# ch559.net
KiCad netlist of a schematic drawn in Altium Designer
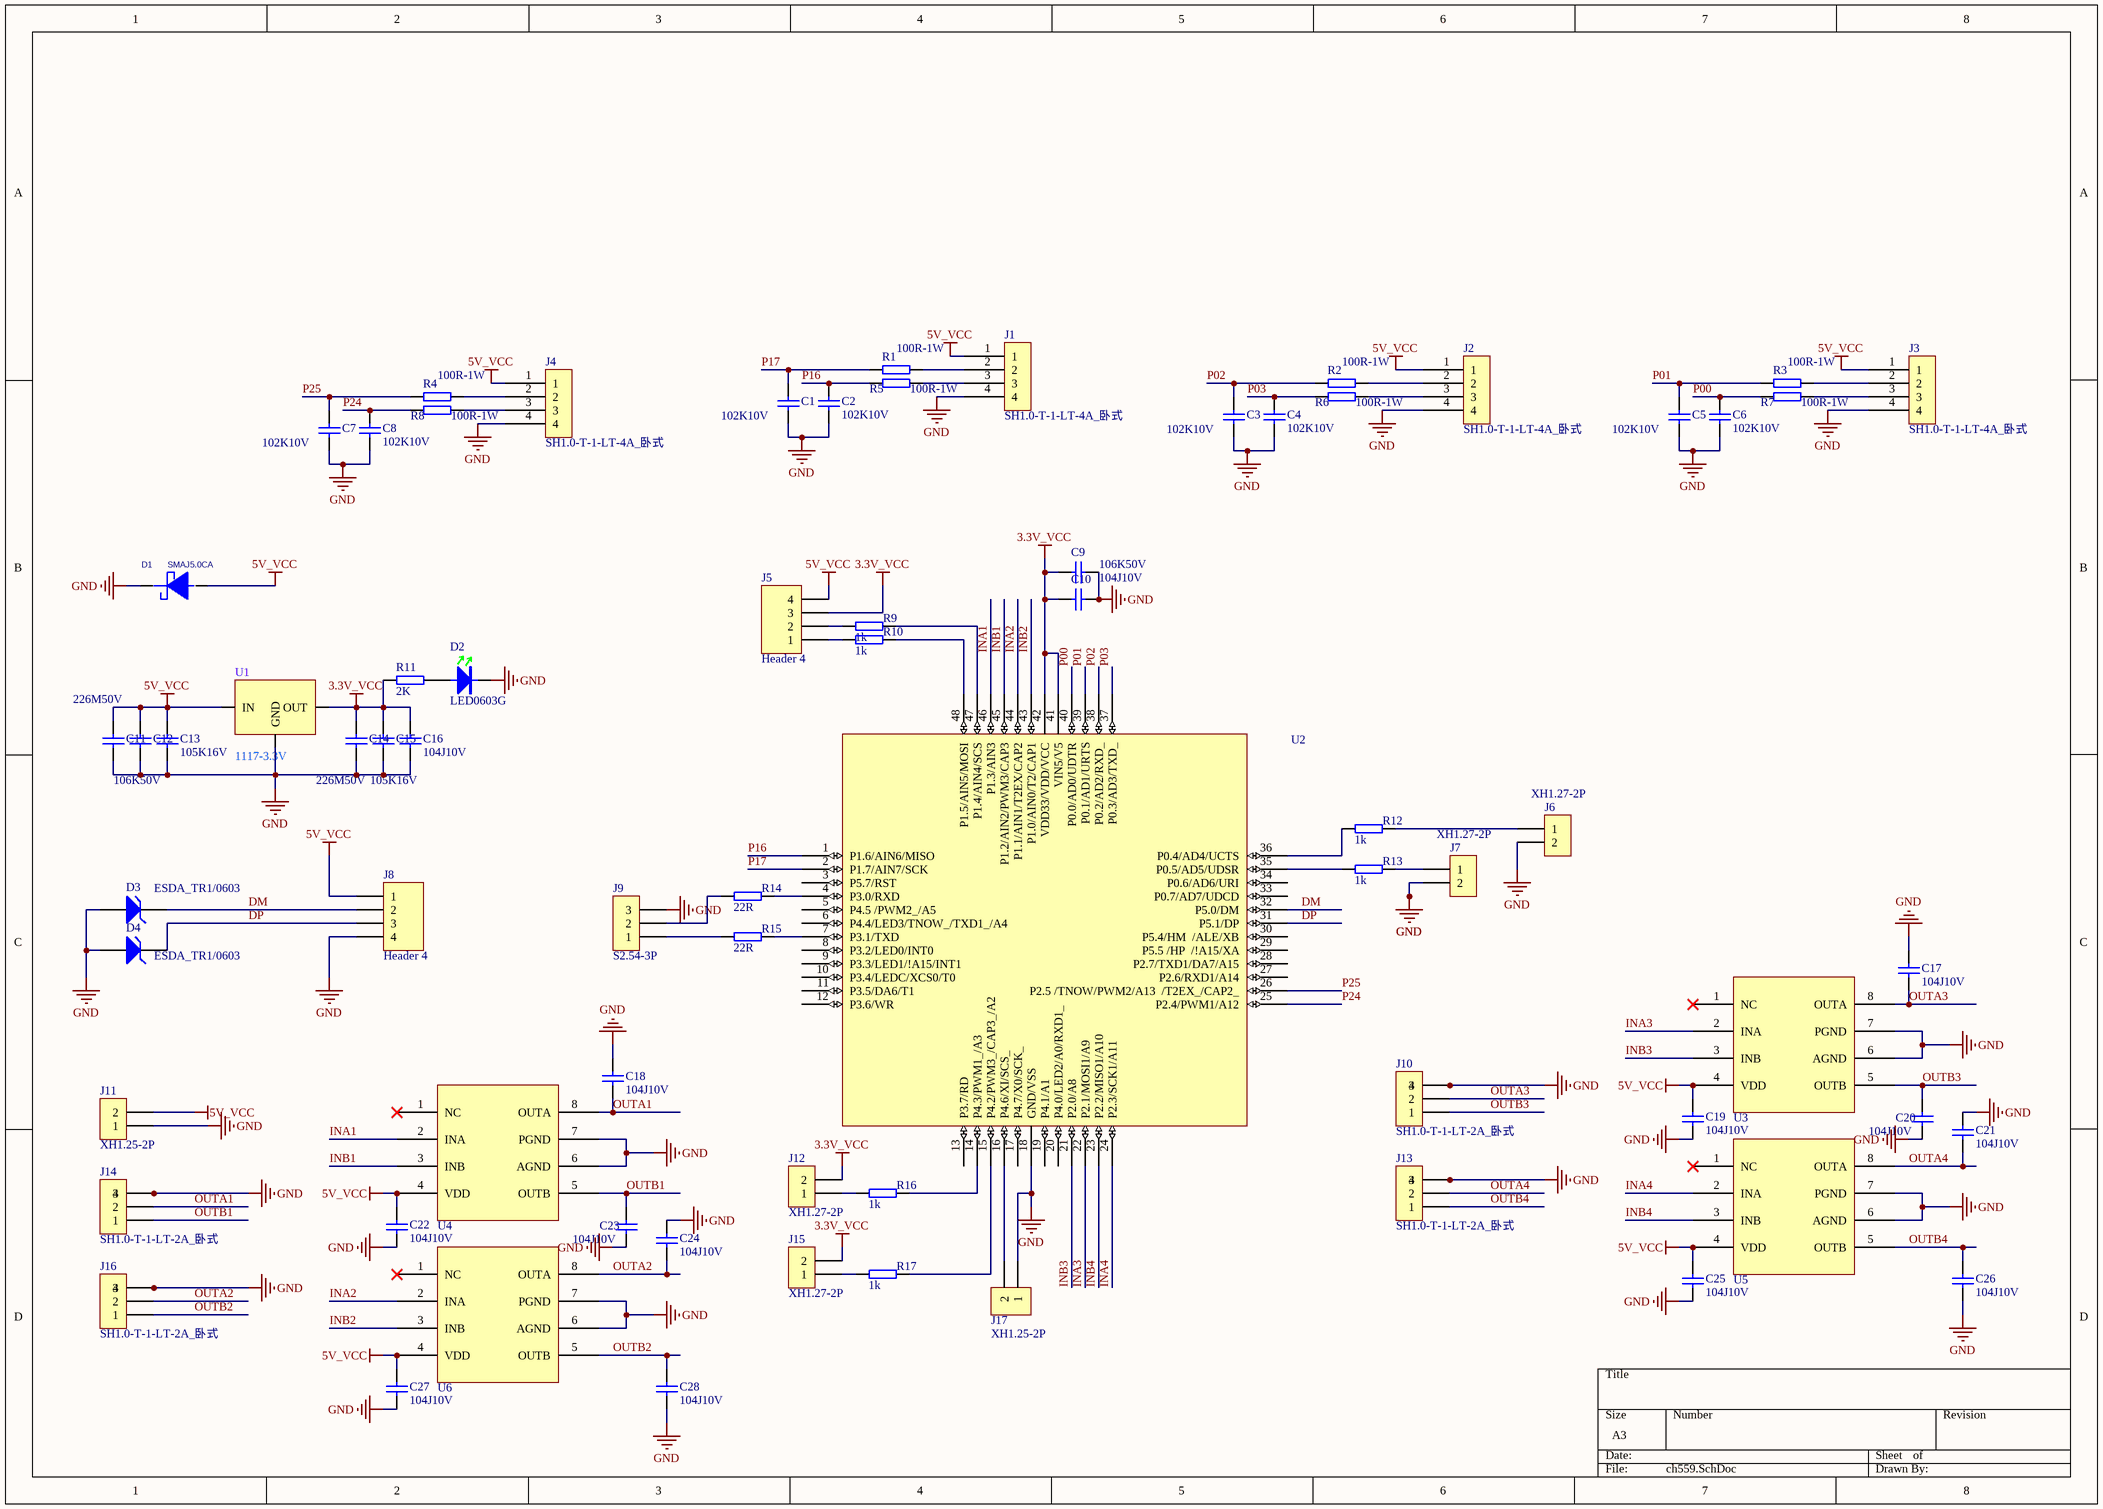
[diagram p0: ch559.SchDoc]

(export (version "E")
  (design (tool "Eeschema 10.0.6"))
  (components
    (comp (ref "C1")
      (value "102K10V")
      (footprint "C0603")
      (description "贴片电容-陶瓷")
      (libsource (lib "Capacitor") (part "C0603X7R-102K10V"))
    )
    (comp (ref "C2")
      (value "102K10V")
      (footprint "C0603")
      (description "贴片电容-陶瓷")
      (libsource (lib "Capacitor") (part "C0603X7R-102K10V"))
    )
    (comp (ref "C3")
      (value "102K10V")
      (footprint "C0603")
      (description "贴片电容-陶瓷")
      (libsource (lib "Capacitor") (part "C0603X7R-102K10V"))
    )
    (comp (ref "C4")
      (value "102K10V")
      (footprint "C0603")
      (description "贴片电容-陶瓷")
      (libsource (lib "Capacitor") (part "C0603X7R-102K10V"))
    )
    (comp (ref "C5")
      (value "102K10V")
      (footprint "C0603")
      (description "贴片电容-陶瓷")
      (libsource (lib "Capacitor") (part "C0603X7R-102K10V"))
    )
    (comp (ref "C6")
      (value "102K10V")
      (footprint "C0603")
      (description "贴片电容-陶瓷")
      (libsource (lib "Capacitor") (part "C0603X7R-102K10V"))
    )
    (comp (ref "C7")
      (value "102K10V")
      (footprint "C0603")
      (description "贴片电容-陶瓷")
      (libsource (lib "Capacitor") (part "C0603X7R-102K10V"))
    )
    (comp (ref "C8")
      (value "102K10V")
      (footprint "C0603")
      (description "贴片电容-陶瓷")
      (libsource (lib "Capacitor") (part "C0603X7R-102K10V"))
    )
    (comp (ref "C9")
      (value "106K50V")
      (footprint "C0603")
      (description "贴片电容-陶瓷")
      (libsource (lib "AIWAC-bolsterV01") (part "C0603X7R-106K50V"))
    )
    (comp (ref "C10")
      (value "104J10V")
      (footprint "C0402")
      (description "贴片电容-陶瓷")
      (libsource (lib "AIWAC-bolsterV01") (part "C0402X7R-104J10V"))
    )
    (comp (ref "C11")
      (value "226M50V")
      (footprint "C0805")
      (description "贴片电容-陶瓷")
      (libsource (lib "AIWAC-bolsterV01") (part "C0805Y5V-226M50V"))
    )
    (comp (ref "C12")
      (value "106K50V")
      (footprint "C0603")
      (description "贴片电容-陶瓷")
      (libsource (lib "AIWAC-bolsterV01") (part "C0603X7R-106K50V"))
    )
    (comp (ref "C13")
      (value "105K16V")
      (footprint "C0603")
      (description "贴片电容-陶瓷")
      (libsource (lib "AIWAC-bolsterV01") (part "C0603X7R-105K16V"))
    )
    (comp (ref "C14")
      (value "226M50V")
      (footprint "C0805")
      (description "贴片电容-陶瓷")
      (libsource (lib "AIWAC-bolsterV01") (part "C0805Y5V-226M50V"))
    )
    (comp (ref "C15")
      (value "105K16V")
      (footprint "C0603")
      (description "贴片电容-陶瓷")
      (libsource (lib "AIWAC-bolsterV01") (part "C0603X7R-105K16V"))
    )
    (comp (ref "C16")
      (value "104J10V")
      (footprint "C0402")
      (description "贴片电容-陶瓷")
      (libsource (lib "AIWAC-bolsterV01") (part "C0402X7R-104J10V"))
    )
    (comp (ref "C17")
      (value "104J10V")
      (footprint "C0402")
      (description "贴片电容-陶瓷")
      (libsource (lib "AIWAC-bolsterV01") (part "C0402X7R-104J10V"))
    )
    (comp (ref "C18")
      (value "104J10V")
      (footprint "C0402")
      (description "贴片电容-陶瓷")
      (libsource (lib "AIWAC-bolsterV01") (part "C0402X7R-104J10V"))
    )
    (comp (ref "C19")
      (value "104J10V")
      (footprint "C0402")
      (description "贴片电容-陶瓷")
      (libsource (lib "AIWAC-bolsterV01") (part "C0402X7R-104J10V"))
    )
    (comp (ref "C20")
      (value "104J10V")
      (footprint "C0402")
      (description "贴片电容-陶瓷")
      (libsource (lib "AIWAC-bolsterV01") (part "C0402X7R-104J10V"))
    )
    (comp (ref "C21")
      (value "104J10V")
      (footprint "C0402")
      (description "贴片电容-陶瓷")
      (libsource (lib "AIWAC-bolsterV01") (part "C0402X7R-104J10V"))
    )
    (comp (ref "C22")
      (value "104J10V")
      (footprint "C0402")
      (description "贴片电容-陶瓷")
      (libsource (lib "AIWAC-bolsterV01") (part "C0402X7R-104J10V"))
    )
    (comp (ref "C23")
      (value "104J10V")
      (footprint "C0402")
      (description "贴片电容-陶瓷")
      (libsource (lib "AIWAC-bolsterV01") (part "C0402X7R-104J10V"))
    )
    (comp (ref "C24")
      (value "104J10V")
      (footprint "C0402")
      (description "贴片电容-陶瓷")
      (libsource (lib "AIWAC-bolsterV01") (part "C0402X7R-104J10V"))
    )
    (comp (ref "C25")
      (value "104J10V")
      (footprint "C0402")
      (description "贴片电容-陶瓷")
      (libsource (lib "AIWAC-bolsterV01") (part "C0402X7R-104J10V"))
    )
    (comp (ref "C26")
      (value "104J10V")
      (footprint "C0402")
      (description "贴片电容-陶瓷")
      (libsource (lib "AIWAC-bolsterV01") (part "C0402X7R-104J10V"))
    )
    (comp (ref "C27")
      (value "104J10V")
      (footprint "C0402")
      (description "贴片电容-陶瓷")
      (libsource (lib "AIWAC-bolsterV01") (part "C0402X7R-104J10V"))
    )
    (comp (ref "C28")
      (value "104J10V")
      (footprint "C0402")
      (description "贴片电容-陶瓷")
      (libsource (lib "AIWAC-bolsterV01") (part "C0402X7R-104J10V"))
    )
    (comp (ref "D1") (value "SMAJ5.0CA") (footprint "DO-214") (libsource (lib "ISO-V3") (part "SMAJ5.0CA")))
    (comp (ref "D2")
      (value "LED0603G")
      (footprint "D-LED0603G")
      (description "贴片二极管-LED")
      (libsource (lib "AIWAC-bolsterV01") (part "DLED-0603-G"))
    )
    (comp (ref "D3")
      (value "ESDA_TR1/0603")
      (footprint "HS_0603D")
      (description "Zener Diode")
      (fields (field (name "PUBLISHER") "*"))
      (libsource (lib "HSC32K1(QFN56)_BlueTooth_V2.0_20171108 - 副本") (part "D Zener"))
    )
    (comp (ref "D4")
      (value "ESDA_TR1/0603")
      (footprint "HS_0603D")
      (description "Zener Diode")
      (fields (field (name "PUBLISHER") "*"))
      (libsource (lib "HSC32K1(QFN56)_BlueTooth_V2.0_20171108 - 副本") (part "D Zener"))
    )
    (comp (ref "J1")
      (value "SH1.0-T-1-LT-4A_卧式")
      (footprint "XH2.54-4P")
      (libsource (lib "Schlib1") (part "SH1.0-T-1-LT-4A_卧式"))
    )
    (comp (ref "J2")
      (value "SH1.0-T-1-LT-4A_卧式")
      (footprint "XH2.54-4P")
      (libsource (lib "Schlib1") (part "SH1.0-T-1-LT-4A_卧式"))
    )
    (comp (ref "J3")
      (value "SH1.0-T-1-LT-4A_卧式")
      (footprint "XH2.54-4P")
      (libsource (lib "Schlib1") (part "SH1.0-T-1-LT-4A_卧式"))
    )
    (comp (ref "J4")
      (value "SH1.0-T-1-LT-4A_卧式")
      (footprint "XH2.54-4P")
      (libsource (lib "Schlib1") (part "SH1.0-T-1-LT-4A_卧式"))
    )
    (comp (ref "J5")
      (value "Header 4")
      (footprint "J-SH1.27 -4")
      (description "Header, 4-Pin")
      (fields (field (name "PUBLISHER") "Altium Limited"))
      (libsource (lib "USB_COM_V1.0") (part "Header 4"))
    )
    (comp (ref "J6")
      (value "XH1.27-2P")
      (footprint "J-SH1.27-2")
      (description "接插件-1.27")
      (libsource (lib "") (part "J-XH1.27-2P_1"))
    )
    (comp (ref "J7")
      (value "XH1.27-2P")
      (footprint "J-SH1.27-2")
      (description "接插件-1.27")
      (libsource (lib "") (part "J-XH1.27-2P_1"))
    )
    (comp (ref "J8")
      (value "Header 4")
      (footprint "XH2.54-4P")
      (description "Header, 4-Pin")
      (fields (field (name "PUBLISHER") "Altium Limited"))
      (libsource (lib "Miscellaneous Connectors") (part "Header 4"))
    )
    (comp (ref "J9")
      (value "S2.54-3P")
      (footprint "S2.54-3P")
      (description "单排排针-直针")
      (libsource (lib "PCB_Project") (part "J-S2.54-3P"))
    )
    (comp (ref "J10")
      (value "SH1.0-T-1-LT-2A_卧式")
      (footprint "J-SH2.0-T-1-LT-2A_立式")
      (libsource (lib "Connector") (part "SH1.0-T-1-LT-2A_卧式"))
    )
    (comp (ref "J11")
      (value "XH1.25-2P")
      (footprint "XH2.54-2p")
      (description "接插件-2.54")
      (libsource (lib "USB_COM_V1.0") (part "J-XH2.54-2P_1"))
    )
    (comp (ref "J12")
      (value "XH1.27-2P")
      (footprint "J-SH1.27-2")
      (description "接插件-1.27")
      (libsource (lib "USB_COM_V1.0") (part "J-XH1.27-2P"))
    )
    (comp (ref "J13")
      (value "SH1.0-T-1-LT-2A_卧式")
      (footprint "J-SH2.0-T-1-LT-2A_立式")
      (libsource (lib "Connector") (part "SH1.0-T-1-LT-2A_卧式"))
    )
    (comp (ref "J14")
      (value "SH1.0-T-1-LT-2A_卧式")
      (footprint "J-SH2.0-T-1-LT-2A_立式")
      (libsource (lib "Connector") (part "SH1.0-T-1-LT-2A_卧式"))
    )
    (comp (ref "J15")
      (value "XH1.27-2P")
      (footprint "J-SH1.27-2")
      (description "接插件-1.27")
      (libsource (lib "USB_COM_V1.0") (part "J-XH1.27-2P"))
    )
    (comp (ref "J16")
      (value "SH1.0-T-1-LT-2A_卧式")
      (footprint "J-SH2.0-T-1-LT-2A_立式")
      (libsource (lib "Connector") (part "SH1.0-T-1-LT-2A_卧式"))
    )
    (comp (ref "J17")
      (value "XH1.25-2P")
      (footprint "S1.25-2P")
      (description "接插件-2.54")
      (libsource (lib "AIWAC-bolsterV01") (part "J-XH2.54-2P"))
    )
    (comp (ref "R1")
      (value "100R-1W")
      (footprint "R0603")
      (description "插件电阻-碳膜")
      (libsource (lib "Resistor") (part "R1-100R"))
    )
    (comp (ref "R2")
      (value "100R-1W")
      (footprint "R0603")
      (description "插件电阻-碳膜")
      (libsource (lib "Resistor") (part "R1-100R"))
    )
    (comp (ref "R3")
      (value "100R-1W")
      (footprint "R0603")
      (description "插件电阻-碳膜")
      (libsource (lib "Resistor") (part "R1-100R"))
    )
    (comp (ref "R4")
      (value "100R-1W")
      (footprint "R0603")
      (description "插件电阻-碳膜")
      (libsource (lib "Resistor") (part "R1-100R"))
    )
    (comp (ref "R5")
      (value "100R-1W")
      (footprint "R0603")
      (description "插件电阻-碳膜")
      (libsource (lib "Resistor") (part "R1-100R"))
    )
    (comp (ref "R6")
      (value "100R-1W")
      (footprint "R0603")
      (description "插件电阻-碳膜")
      (libsource (lib "Resistor") (part "R1-100R"))
    )
    (comp (ref "R7")
      (value "100R-1W")
      (footprint "R0603")
      (description "插件电阻-碳膜")
      (libsource (lib "Resistor") (part "R1-100R"))
    )
    (comp (ref "R8")
      (value "100R-1W")
      (footprint "R0603")
      (description "插件电阻-碳膜")
      (libsource (lib "Resistor") (part "R1-100R"))
    )
    (comp (ref "R9")
      (value "1k")
      (footprint "R0603")
      (description "贴片电阻-通用")
      (libsource (lib "Resistor") (part "R0603-100RF"))
    )
    (comp (ref "R10")
      (value "1k")
      (footprint "R0603")
      (description "贴片电阻-通用")
      (libsource (lib "Resistor") (part "R0603-100RF"))
    )
    (comp (ref "R11")
      (value "2K")
      (footprint "R0603")
      (description "贴片电阻-通用")
      (libsource (lib "Resistor") (part "R0603-100RF"))
    )
    (comp (ref "R12")
      (value "1k")
      (footprint "R0603")
      (description "贴片电阻-通用")
      (libsource (lib "Resistor") (part "R0603-100RF"))
    )
    (comp (ref "R13")
      (value "1k")
      (footprint "R0603")
      (description "贴片电阻-通用")
      (libsource (lib "Resistor") (part "R0603-100RF"))
    )
    (comp (ref "R14")
      (value "22R")
      (footprint "R0603")
      (description "贴片电阻-通用")
      (libsource (lib "Resistor") (part "R0603-100RF"))
    )
    (comp (ref "R15")
      (value "22R")
      (footprint "R0603")
      (description "贴片电阻-通用")
      (libsource (lib "Resistor") (part "R0603-100RF"))
    )
    (comp (ref "R16")
      (value "1k")
      (footprint "R0603")
      (description "贴片电阻-通用")
      (libsource (lib "Resistor") (part "R0603-100RF"))
    )
    (comp (ref "R17")
      (value "1k")
      (footprint "R0603")
      (description "贴片电阻-通用")
      (libsource (lib "Resistor") (part "R0603-100RF"))
    )
    (comp (ref "U1")
      (value "1117-3.3V")
      (footprint "SOT-223")
      (description "芯片 电源类")
      (libsource (lib "标准通用原理图库") (part "AP1117-33 SOT-223"))
    )
    (comp (ref "U2")
      (value "CH559L")
      (footprint "LQFP48")
      (description "单片机")
      (libsource (lib "PCB_Project") (part "CH559L"))
    )
    (comp (ref "U3")
      (value "PTC918")
      (footprint "SO-8")
      (description "马达驱动芯片")
      (libsource (lib "USB_COM_V1.0") (part "PTC918"))
    )
    (comp (ref "U4")
      (value "PTC918")
      (footprint "SO-8")
      (description "马达驱动芯片")
      (libsource (lib "USB_COM_V1.0") (part "PTC918"))
    )
    (comp (ref "U5")
      (value "PTC918")
      (footprint "SO-8")
      (description "马达驱动芯片")
      (libsource (lib "USB_COM_V1.0") (part "PTC918"))
    )
    (comp (ref "U6")
      (value "PTC918")
      (footprint "SO-8")
      (description "马达驱动芯片")
      (libsource (lib "USB_COM_V1.0") (part "PTC918"))
    )
  )
  (nets
    (net (code "1") (name "/DM") (class "Default")
      (node (ref "D3") (pin "2") (pinfunction "K_2") (pintype "passive"))
      (node (ref "J8") (pin "2") (pinfunction "2_2") (pintype "passive"))
      (node (ref "U2") (pin "32") (pinfunction "P5.0/DM_32") (pintype "bidirectional"))
    )
    (net (code "2") (name "/DP") (class "Default")
      (node (ref "D4") (pin "2") (pinfunction "K_2") (pintype "passive"))
      (node (ref "J8") (pin "3") (pinfunction "3_3") (pintype "passive"))
      (node (ref "U2") (pin "31") (pinfunction "P5.1/DP_31") (pintype "bidirectional"))
    )
    (net (code "3") (name "/INA1") (class "Default")
      (node (ref "U2") (pin "46") (pinfunction "P1.3/AIN3_46") (pintype "bidirectional"))
      (node (ref "U4") (pin "2") (pinfunction "INA_2") (pintype "passive"))
    )
    (net (code "4") (name "/INA2") (class "Default")
      (node (ref "U2") (pin "44") (pinfunction "P1.1/AIN1/T2EX/CAP2_44") (pintype "bidirectional"))
      (node (ref "U6") (pin "2") (pinfunction "INA_2") (pintype "passive"))
    )
    (net (code "5") (name "/INA3") (class "Default")
      (node (ref "U2") (pin "22") (pinfunction "P2.1/MOSI1/A9_22") (pintype "bidirectional"))
      (node (ref "U3") (pin "2") (pinfunction "INA_2") (pintype "passive"))
    )
    (net (code "6") (name "/INA4") (class "Default")
      (node (ref "U2") (pin "24") (pinfunction "P2.3/SCK1/A11_24") (pintype "bidirectional"))
      (node (ref "U5") (pin "2") (pinfunction "INA_2") (pintype "passive"))
    )
    (net (code "7") (name "/INB1") (class "Default")
      (node (ref "U2") (pin "45") (pinfunction "P1.2/AIN2/PWM3/CAP3_45") (pintype "bidirectional"))
      (node (ref "U4") (pin "3") (pinfunction "INB_3") (pintype "passive"))
    )
    (net (code "8") (name "/INB2") (class "Default")
      (node (ref "U2") (pin "43") (pinfunction "P1.0/AIN0/T2/CAP1_43") (pintype "bidirectional"))
      (node (ref "U6") (pin "3") (pinfunction "INB_3") (pintype "passive"))
    )
    (net (code "9") (name "/INB3") (class "Default")
      (node (ref "U2") (pin "21") (pinfunction "P2.0/A8_21") (pintype "bidirectional"))
      (node (ref "U3") (pin "3") (pinfunction "INB_3") (pintype "passive"))
    )
    (net (code "10") (name "/INB4") (class "Default")
      (node (ref "U2") (pin "23") (pinfunction "P2.2/MISO1/A10_23") (pintype "bidirectional"))
      (node (ref "U5") (pin "3") (pinfunction "INB_3") (pintype "passive"))
    )
    (net (code "11") (name "/OUTA1") (class "Default")
      (node (ref "C18") (pin "2") (pinfunction "2_2") (pintype "passive"))
      (node (ref "J14") (pin "2") (pinfunction "2_2") (pintype "passive"))
      (node (ref "U4") (pin "8") (pinfunction "OUTA_8") (pintype "passive"))
    )
    (net (code "12") (name "/OUTA2") (class "Default")
      (node (ref "C24") (pin "2") (pinfunction "2_2") (pintype "passive"))
      (node (ref "J16") (pin "2") (pinfunction "2_2") (pintype "passive"))
      (node (ref "U6") (pin "8") (pinfunction "OUTA_8") (pintype "passive"))
    )
    (net (code "13") (name "/OUTA3") (class "Default")
      (node (ref "C17") (pin "2") (pinfunction "2_2") (pintype "passive"))
      (node (ref "J10") (pin "2") (pinfunction "2_2") (pintype "passive"))
      (node (ref "U3") (pin "8") (pinfunction "OUTA_8") (pintype "passive"))
    )
    (net (code "14") (name "/OUTA4") (class "Default")
      (node (ref "C21") (pin "2") (pinfunction "2_2") (pintype "passive"))
      (node (ref "J13") (pin "2") (pinfunction "2_2") (pintype "passive"))
      (node (ref "U5") (pin "8") (pinfunction "OUTA_8") (pintype "passive"))
    )
    (net (code "15") (name "/OUTB1") (class "Default")
      (node (ref "C23") (pin "1") (pinfunction "1_1") (pintype "passive"))
      (node (ref "J14") (pin "1") (pinfunction "1_1") (pintype "passive"))
      (node (ref "U4") (pin "5") (pinfunction "OUTB_5") (pintype "passive"))
    )
    (net (code "16") (name "/OUTB2") (class "Default")
      (node (ref "C28") (pin "1") (pinfunction "1_1") (pintype "passive"))
      (node (ref "J16") (pin "1") (pinfunction "1_1") (pintype "passive"))
      (node (ref "U6") (pin "5") (pinfunction "OUTB_5") (pintype "passive"))
    )
    (net (code "17") (name "/OUTB3") (class "Default")
      (node (ref "C20") (pin "1") (pinfunction "1_1") (pintype "passive"))
      (node (ref "J10") (pin "1") (pinfunction "1_1") (pintype "passive"))
      (node (ref "U3") (pin "5") (pinfunction "OUTB_5") (pintype "passive"))
    )
    (net (code "18") (name "/OUTB4") (class "Default")
      (node (ref "C26") (pin "1") (pinfunction "1_1") (pintype "passive"))
      (node (ref "J13") (pin "1") (pinfunction "1_1") (pintype "passive"))
      (node (ref "U5") (pin "5") (pinfunction "OUTB_5") (pintype "passive"))
    )
    (net (code "19") (name "/P00") (class "Default")
      (node (ref "C6") (pin "1") (pinfunction "1_1") (pintype "passive"))
      (node (ref "R7") (pin "1") (pinfunction "1_1") (pintype "passive"))
      (node (ref "U2") (pin "40") (pinfunction "P0.0/AD0/UDTR_40") (pintype "bidirectional"))
    )
    (net (code "20") (name "/P01") (class "Default")
      (node (ref "C5") (pin "1") (pinfunction "1_1") (pintype "passive"))
      (node (ref "R3") (pin "1") (pinfunction "1_1") (pintype "passive"))
      (node (ref "U2") (pin "39") (pinfunction "P0.1/AD1/URTS_39") (pintype "bidirectional"))
    )
    (net (code "21") (name "/P02") (class "Default")
      (node (ref "C3") (pin "1") (pinfunction "1_1") (pintype "passive"))
      (node (ref "R2") (pin "1") (pinfunction "1_1") (pintype "passive"))
      (node (ref "U2") (pin "38") (pinfunction "P0.2/AD2/RXD__38") (pintype "bidirectional"))
    )
    (net (code "22") (name "/P03") (class "Default")
      (node (ref "C4") (pin "1") (pinfunction "1_1") (pintype "passive"))
      (node (ref "R6") (pin "1") (pinfunction "1_1") (pintype "passive"))
      (node (ref "U2") (pin "37") (pinfunction "P0.3/AD3/TXD__37") (pintype "bidirectional"))
    )
    (net (code "23") (name "/P16") (class "Default")
      (node (ref "C2") (pin "1") (pinfunction "1_1") (pintype "passive"))
      (node (ref "R5") (pin "1") (pinfunction "1_1") (pintype "passive"))
      (node (ref "U2") (pin "1") (pinfunction "P1.6/AIN6/MISO_1") (pintype "bidirectional"))
    )
    (net (code "24") (name "/P17") (class "Default")
      (node (ref "C1") (pin "1") (pinfunction "1_1") (pintype "passive"))
      (node (ref "R1") (pin "1") (pinfunction "1_1") (pintype "passive"))
      (node (ref "U2") (pin "2") (pinfunction "P1.7/AIN7/SCK_2") (pintype "bidirectional"))
    )
    (net (code "25") (name "/P24") (class "Default")
      (node (ref "C8") (pin "1") (pinfunction "1_1") (pintype "passive"))
      (node (ref "R8") (pin "1") (pinfunction "1_1") (pintype "passive"))
      (node (ref "U2") (pin "25") (pinfunction "P2.4/PWM1/A12_25") (pintype "bidirectional"))
    )
    (net (code "26") (name "/P25") (class "Default")
      (node (ref "C7") (pin "1") (pinfunction "1_1") (pintype "passive"))
      (node (ref "R4") (pin "1") (pinfunction "1_1") (pintype "passive"))
      (node (ref "U2") (pin "26") (pinfunction "P2.5_/TNOW/PWM2/A13__/T2EX_/CAP2__26") (pintype "bidirectional"))
    )
    (net (code "27") (name "3.3V_VCC") (class "Default")
      (node (ref "C10") (pin "2") (pinfunction "2_2") (pintype "passive"))
      (node (ref "C14") (pin "1") (pinfunction "1_1") (pintype "passive"))
      (node (ref "C15") (pin "2") (pinfunction "2_2") (pintype "passive"))
      (node (ref "C16") (pin "1") (pinfunction "1_1") (pintype "passive"))
      (node (ref "C9") (pin "2") (pinfunction "2_2") (pintype "passive"))
      (node (ref "J12") (pin "2") (pinfunction "2_2") (pintype "passive"))
      (node (ref "J15") (pin "2") (pinfunction "2_2") (pintype "passive"))
      (node (ref "J5") (pin "3") (pinfunction "3_3") (pintype "passive"))
      (node (ref "R11") (pin "2") (pinfunction "2_2") (pintype "passive"))
      (node (ref "U1") (pin "2") (pinfunction "OUT_2") (pintype "passive"))
      (node (ref "U2") (pin "41") (pinfunction "VIN5/V5_41") (pintype "passive"))
      (node (ref "U2") (pin "42") (pinfunction "VDD33/VDD/VCC_42") (pintype "passive"))
    )
    (net (code "28") (name "5V_VCC") (class "Default")
      (node (ref "C11") (pin "1") (pinfunction "1_1") (pintype "passive"))
      (node (ref "C12") (pin "1") (pinfunction "1_1") (pintype "passive"))
      (node (ref "C13") (pin "1") (pinfunction "1_1") (pintype "passive"))
      (node (ref "C19") (pin "1") (pinfunction "1_1") (pintype "passive"))
      (node (ref "C22") (pin "1") (pinfunction "1_1") (pintype "passive"))
      (node (ref "C25") (pin "1") (pinfunction "1_1") (pintype "passive"))
      (node (ref "C27") (pin "1") (pinfunction "1_1") (pintype "passive"))
      (node (ref "D1") (pin "1") (pinfunction "+_1") (pintype "passive"))
      (node (ref "J1") (pin "1") (pinfunction "1_1") (pintype "passive"))
      (node (ref "J11") (pin "2") (pinfunction "2_2") (pintype "passive"))
      (node (ref "J2") (pin "1") (pinfunction "1_1") (pintype "passive"))
      (node (ref "J3") (pin "1") (pinfunction "1_1") (pintype "passive"))
      (node (ref "J4") (pin "1") (pinfunction "1_1") (pintype "passive"))
      (node (ref "J5") (pin "4") (pinfunction "4_4") (pintype "passive"))
      (node (ref "J8") (pin "1") (pinfunction "1_1") (pintype "passive"))
      (node (ref "U1") (pin "3") (pinfunction "IN_3") (pintype "passive"))
      (node (ref "U3") (pin "4") (pinfunction "VDD_4") (pintype "passive"))
      (node (ref "U4") (pin "4") (pinfunction "VDD_4") (pintype "passive"))
      (node (ref "U5") (pin "4") (pinfunction "VDD_4") (pintype "passive"))
      (node (ref "U6") (pin "4") (pinfunction "VDD_4") (pintype "passive"))
    )
    (net (code "29") (name "GND") (class "Default")
      (node (ref "C1") (pin "2") (pinfunction "2_2") (pintype "passive"))
      (node (ref "C10") (pin "1") (pinfunction "1_1") (pintype "passive"))
      (node (ref "C11") (pin "2") (pinfunction "2_2") (pintype "passive"))
      (node (ref "C12") (pin "2") (pinfunction "2_2") (pintype "passive"))
      (node (ref "C13") (pin "2") (pinfunction "2_2") (pintype "passive"))
      (node (ref "C14") (pin "2") (pinfunction "2_2") (pintype "passive"))
      (node (ref "C15") (pin "1") (pinfunction "1_1") (pintype "passive"))
      (node (ref "C16") (pin "2") (pinfunction "2_2") (pintype "passive"))
      (node (ref "C17") (pin "1") (pinfunction "1_1") (pintype "passive"))
      (node (ref "C18") (pin "1") (pinfunction "1_1") (pintype "passive"))
      (node (ref "C19") (pin "2") (pinfunction "2_2") (pintype "passive"))
      (node (ref "C2") (pin "2") (pinfunction "2_2") (pintype "passive"))
      (node (ref "C20") (pin "2") (pinfunction "2_2") (pintype "passive"))
      (node (ref "C21") (pin "1") (pinfunction "1_1") (pintype "passive"))
      (node (ref "C22") (pin "2") (pinfunction "2_2") (pintype "passive"))
      (node (ref "C23") (pin "2") (pinfunction "2_2") (pintype "passive"))
      (node (ref "C24") (pin "1") (pinfunction "1_1") (pintype "passive"))
      (node (ref "C25") (pin "2") (pinfunction "2_2") (pintype "passive"))
      (node (ref "C26") (pin "2") (pinfunction "2_2") (pintype "passive"))
      (node (ref "C27") (pin "2") (pinfunction "2_2") (pintype "passive"))
      (node (ref "C28") (pin "2") (pinfunction "2_2") (pintype "passive"))
      (node (ref "C3") (pin "2") (pinfunction "2_2") (pintype "passive"))
      (node (ref "C4") (pin "2") (pinfunction "2_2") (pintype "passive"))
      (node (ref "C5") (pin "2") (pinfunction "2_2") (pintype "passive"))
      (node (ref "C6") (pin "2") (pinfunction "2_2") (pintype "passive"))
      (node (ref "C7") (pin "2") (pinfunction "2_2") (pintype "passive"))
      (node (ref "C8") (pin "2") (pinfunction "2_2") (pintype "passive"))
      (node (ref "C9") (pin "1") (pinfunction "1_1") (pintype "passive"))
      (node (ref "D1") (pin "2") (pinfunction "-_2") (pintype "passive"))
      (node (ref "D2") (pin "2") (pinfunction "2_2") (pintype "passive"))
      (node (ref "D3") (pin "1") (pinfunction "A_1") (pintype "passive"))
      (node (ref "D4") (pin "1") (pinfunction "A_1") (pintype "passive"))
      (node (ref "J1") (pin "4") (pinfunction "4_4") (pintype "passive"))
      (node (ref "J10") (pin "3") (pinfunction "3_3") (pintype "passive"))
      (node (ref "J10") (pin "4") (pinfunction "4_4") (pintype "passive"))
      (node (ref "J11") (pin "1") (pinfunction "1_1") (pintype "passive"))
      (node (ref "J13") (pin "3") (pinfunction "3_3") (pintype "passive"))
      (node (ref "J13") (pin "4") (pinfunction "4_4") (pintype "passive"))
      (node (ref "J14") (pin "3") (pinfunction "3_3") (pintype "passive"))
      (node (ref "J14") (pin "4") (pinfunction "4_4") (pintype "passive"))
      (node (ref "J16") (pin "3") (pinfunction "3_3") (pintype "passive"))
      (node (ref "J16") (pin "4") (pinfunction "4_4") (pintype "passive"))
      (node (ref "J17") (pin "1") (pinfunction "1_1") (pintype "passive"))
      (node (ref "J2") (pin "4") (pinfunction "4_4") (pintype "passive"))
      (node (ref "J3") (pin "4") (pinfunction "4_4") (pintype "passive"))
      (node (ref "J4") (pin "4") (pinfunction "4_4") (pintype "passive"))
      (node (ref "J6") (pin "2") (pinfunction "2_2") (pintype "passive"))
      (node (ref "J7") (pin "2") (pinfunction "2_2") (pintype "passive"))
      (node (ref "J8") (pin "4") (pinfunction "4_4") (pintype "passive"))
      (node (ref "J9") (pin "3") (pinfunction "3_3") (pintype "passive"))
      (node (ref "U1") (pin "1") (pinfunction "GND_1") (pintype "passive"))
      (node (ref "U2") (pin "18") (pinfunction "GND/VSS_18") (pintype "passive"))
      (node (ref "U3") (pin "6") (pinfunction "AGND_6") (pintype "passive"))
      (node (ref "U3") (pin "7") (pinfunction "PGND_7") (pintype "passive"))
      (node (ref "U4") (pin "6") (pinfunction "AGND_6") (pintype "passive"))
      (node (ref "U4") (pin "7") (pinfunction "PGND_7") (pintype "passive"))
      (node (ref "U5") (pin "6") (pinfunction "AGND_6") (pintype "passive"))
      (node (ref "U5") (pin "7") (pinfunction "PGND_7") (pintype "passive"))
      (node (ref "U6") (pin "6") (pinfunction "AGND_6") (pintype "passive"))
      (node (ref "U6") (pin "7") (pinfunction "PGND_7") (pintype "passive"))
    )
    (net (code "30") (name "Net-(D2-Pad1)") (class "Default")
      (node (ref "D2") (pin "1") (pinfunction "1_1") (pintype "passive"))
      (node (ref "R11") (pin "1") (pinfunction "1_1") (pintype "passive"))
    )
    (net (code "31") (name "Net-(J1-Pad2)") (class "Default")
      (node (ref "J1") (pin "2") (pinfunction "2_2") (pintype "passive"))
      (node (ref "R1") (pin "2") (pinfunction "2_2") (pintype "passive"))
    )
    (net (code "32") (name "Net-(J1-Pad3)") (class "Default")
      (node (ref "J1") (pin "3") (pinfunction "3_3") (pintype "passive"))
      (node (ref "R5") (pin "2") (pinfunction "2_2") (pintype "passive"))
    )
    (net (code "33") (name "Net-(J2-Pad2)") (class "Default")
      (node (ref "J2") (pin "2") (pinfunction "2_2") (pintype "passive"))
      (node (ref "R2") (pin "2") (pinfunction "2_2") (pintype "passive"))
    )
    (net (code "34") (name "Net-(J2-Pad3)") (class "Default")
      (node (ref "J2") (pin "3") (pinfunction "3_3") (pintype "passive"))
      (node (ref "R6") (pin "2") (pinfunction "2_2") (pintype "passive"))
    )
    (net (code "35") (name "Net-(J3-Pad2)") (class "Default")
      (node (ref "J3") (pin "2") (pinfunction "2_2") (pintype "passive"))
      (node (ref "R3") (pin "2") (pinfunction "2_2") (pintype "passive"))
    )
    (net (code "36") (name "Net-(J3-Pad3)") (class "Default")
      (node (ref "J3") (pin "3") (pinfunction "3_3") (pintype "passive"))
      (node (ref "R7") (pin "2") (pinfunction "2_2") (pintype "passive"))
    )
    (net (code "37") (name "Net-(J4-Pad2)") (class "Default")
      (node (ref "J4") (pin "2") (pinfunction "2_2") (pintype "passive"))
      (node (ref "R4") (pin "2") (pinfunction "2_2") (pintype "passive"))
    )
    (net (code "38") (name "Net-(J4-Pad3)") (class "Default")
      (node (ref "J4") (pin "3") (pinfunction "3_3") (pintype "passive"))
      (node (ref "R8") (pin "2") (pinfunction "2_2") (pintype "passive"))
    )
    (net (code "39") (name "Net-(J5-Pad1)") (class "Default")
      (node (ref "J5") (pin "1") (pinfunction "1_1") (pintype "passive"))
      (node (ref "R10") (pin "1") (pinfunction "1_1") (pintype "passive"))
    )
    (net (code "40") (name "Net-(J5-Pad2)") (class "Default")
      (node (ref "J5") (pin "2") (pinfunction "2_2") (pintype "passive"))
      (node (ref "R9") (pin "1") (pinfunction "1_1") (pintype "passive"))
    )
    (net (code "41") (name "Net-(J6-Pad1)") (class "Default")
      (node (ref "J6") (pin "1") (pinfunction "1_1") (pintype "passive"))
      (node (ref "R12") (pin "2") (pinfunction "2_2") (pintype "passive"))
    )
    (net (code "42") (name "Net-(J7-Pad1)") (class "Default")
      (node (ref "J7") (pin "1") (pinfunction "1_1") (pintype "passive"))
      (node (ref "R13") (pin "2") (pinfunction "2_2") (pintype "passive"))
    )
    (net (code "43") (name "Net-(J9-Pad1)") (class "Default")
      (node (ref "J9") (pin "1") (pinfunction "1_1") (pintype "passive"))
      (node (ref "R15") (pin "1") (pinfunction "1_1") (pintype "passive"))
    )
    (net (code "44") (name "Net-(J9-Pad2)") (class "Default")
      (node (ref "J9") (pin "2") (pinfunction "2_2") (pintype "passive"))
      (node (ref "R14") (pin "1") (pinfunction "1_1") (pintype "passive"))
    )
    (net (code "45") (name "Net-(J12-Pad1)") (class "Default")
      (node (ref "J12") (pin "1") (pinfunction "1_1") (pintype "passive"))
      (node (ref "R16") (pin "1") (pinfunction "1_1") (pintype "passive"))
    )
    (net (code "46") (name "Net-(J15-Pad1)") (class "Default")
      (node (ref "J15") (pin "1") (pinfunction "1_1") (pintype "passive"))
      (node (ref "R17") (pin "1") (pinfunction "1_1") (pintype "passive"))
    )
    (net (code "47") (name "Net-(U2-P0.4{slash}AD4{slash}UCTS)") (class "Default")
      (node (ref "R12") (pin "1") (pinfunction "1_1") (pintype "passive"))
      (node (ref "U2") (pin "36") (pinfunction "P0.4/AD4/UCTS_36") (pintype "bidirectional"))
    )
    (net (code "48") (name "Net-(U2-P0.5{slash}AD5{slash}UDSR)") (class "Default")
      (node (ref "R13") (pin "1") (pinfunction "1_1") (pintype "passive"))
      (node (ref "U2") (pin "35") (pinfunction "P0.5/AD5/UDSR_35") (pintype "bidirectional"))
    )
    (net (code "49") (name "Net-(U2-P1.4{slash}AIN4{slash}SCS)") (class "Default")
      (node (ref "R9") (pin "2") (pinfunction "2_2") (pintype "passive"))
      (node (ref "U2") (pin "47") (pinfunction "P1.4/AIN4/SCS_47") (pintype "bidirectional"))
    )
    (net (code "50") (name "Net-(U2-P1.5{slash}AIN5{slash}MOSI)") (class "Default")
      (node (ref "R10") (pin "2") (pinfunction "2_2") (pintype "passive"))
      (node (ref "U2") (pin "48") (pinfunction "P1.5/AIN5/MOSI_48") (pintype "bidirectional"))
    )
    (net (code "51") (name "Net-(U2-P3.0{slash}RXD)") (class "Default")
      (node (ref "R14") (pin "2") (pinfunction "2_2") (pintype "passive"))
      (node (ref "U2") (pin "4") (pinfunction "P3.0/RXD_4") (pintype "bidirectional"))
    )
    (net (code "52") (name "Net-(U2-P3.1{slash}TXD)") (class "Default")
      (node (ref "R15") (pin "2") (pinfunction "2_2") (pintype "passive"))
      (node (ref "U2") (pin "7") (pinfunction "P3.1/TXD_7") (pintype "bidirectional"))
    )
    (net (code "53") (name "Net-(U2-P4.2{slash}PWM3_{slash}CAP3_{slash}A2)") (class "Default")
      (node (ref "R17") (pin "2") (pinfunction "2_2") (pintype "passive"))
      (node (ref "U2") (pin "15") (pinfunction "P4.2/PWM3_/CAP3_/A2_15") (pintype "bidirectional"))
    )
    (net (code "54") (name "Net-(U2-P4.3{slash}PWM1_{slash}A3)") (class "Default")
      (node (ref "R16") (pin "2") (pinfunction "2_2") (pintype "passive"))
      (node (ref "U2") (pin "14") (pinfunction "P4.3/PWM1_/A3_14") (pintype "bidirectional"))
    )
    (net (code "55") (name "Net-(U2-P4.6{slash}XI{slash}SCS_)") (class "Default")
      (node (ref "J17") (pin "2") (pinfunction "2_2") (pintype "passive"))
      (node (ref "U2") (pin "16") (pinfunction "P4.6/XI/SCS__16") (pintype "bidirectional"))
    )
    (net (code "56") (name "unconnected-(U2-P0.6{slash}AD6{slash}URI-Pad34)") (class "Default")
      (node (ref "U2") (pin "34") (pinfunction "P0.6/AD6/URI_34") (pintype "bidirectional"))
    )
    (net (code "57") (name "unconnected-(U2-P0.7{slash}AD7{slash}UDCD-Pad33)") (class "Default")
      (node (ref "U2") (pin "33") (pinfunction "P0.7/AD7/UDCD_33") (pintype "bidirectional"))
    )
    (net (code "58") (name "unconnected-(U2-P2.6{slash}RXD1{slash}A14-Pad27)") (class "Default")
      (node (ref "U2") (pin "27") (pinfunction "P2.6/RXD1/A14_27") (pintype "bidirectional"))
    )
    (net (code "59") (name "unconnected-(U2-P2.7{slash}TXD1{slash}DA7{slash}A15-Pad28)") (class "Default")
      (node (ref "U2") (pin "28") (pinfunction "P2.7/TXD1/DA7/A15_28") (pintype "bidirectional"))
    )
    (net (code "60") (name "unconnected-(U2-P3.2{slash}LED0{slash}INT0-Pad8)") (class "Default")
      (node (ref "U2") (pin "8") (pinfunction "P3.2/LED0/INT0_8") (pintype "bidirectional"))
    )
    (net (code "61") (name "unconnected-(U2-P3.3{slash}LED1{slash}!A15{slash}INT1-Pad9)") (class "Default")
      (node (ref "U2") (pin "9") (pinfunction "P3.3/LED1/!A15/INT1_9") (pintype "bidirectional"))
    )
    (net (code "62") (name "unconnected-(U2-P3.4{slash}LEDC{slash}XCS0{slash}T0-Pad10)") (class "Default")
      (node (ref "U2") (pin "10") (pinfunction "P3.4/LEDC/XCS0/T0_10") (pintype "bidirectional"))
    )
    (net (code "63") (name "unconnected-(U2-P3.5{slash}DA6{slash}T1-Pad11)") (class "Default")
      (node (ref "U2") (pin "11") (pinfunction "P3.5/DA6/T1_11") (pintype "bidirectional"))
    )
    (net (code "64") (name "unconnected-(U2-P3.6{slash}WR-Pad12)") (class "Default")
      (node (ref "U2") (pin "12") (pinfunction "P3.6/WR_12") (pintype "bidirectional"))
    )
    (net (code "65") (name "unconnected-(U2-P3.7{slash}RD-Pad13)") (class "Default")
      (node (ref "U2") (pin "13") (pinfunction "P3.7/RD_13") (pintype "bidirectional"))
    )
    (net (code "66") (name "unconnected-(U2-P4.0{slash}LED2{slash}A0{slash}RXD1_-Pad20)") (class "Default")
      (node (ref "U2") (pin "20") (pinfunction "P4.0/LED2/A0/RXD1__20") (pintype "bidirectional"))
    )
    (net (code "67") (name "unconnected-(U2-P4.1{slash}A1-Pad19)") (class "Default")
      (node (ref "U2") (pin "19") (pinfunction "P4.1/A1_19") (pintype "bidirectional"))
    )
    (net (code "68") (name "unconnected-(U2-P4.4{slash}LED3{slash}TNOW_{slash}TXD1_{slash}A4-Pad6)") (class "Default")
      (node (ref "U2") (pin "6") (pinfunction "P4.4/LED3/TNOW_/TXD1_/A4_6") (pintype "bidirectional"))
    )
    (net (code "69") (name "unconnected-(U2-P4.5_{slash}PWM2_{slash}A5-Pad5)") (class "Default")
      (node (ref "U2") (pin "5") (pinfunction "P4.5_/PWM2_/A5_5") (pintype "bidirectional"))
    )
    (net (code "70") (name "unconnected-(U2-P4.7{slash}X0{slash}SCK_-Pad17)") (class "Default")
      (node (ref "U2") (pin "17") (pinfunction "P4.7/X0/SCK__17") (pintype "bidirectional"))
    )
    (net (code "71") (name "unconnected-(U2-P5.4{slash}HM__{slash}ALE{slash}XB-Pad30)") (class "Default")
      (node (ref "U2") (pin "30") (pinfunction "P5.4/HM__/ALE/XB_30") (pintype "bidirectional"))
    )
    (net (code "72") (name "unconnected-(U2-P5.5_{slash}HP__{slash}!A15{slash}XA-Pad29)") (class "Default")
      (node (ref "U2") (pin "29") (pinfunction "P5.5_/HP__/!A15/XA_29") (pintype "bidirectional"))
    )
    (net (code "73") (name "unconnected-(U2-P5.7{slash}RST-Pad3)") (class "Default")
      (node (ref "U2") (pin "3") (pinfunction "P5.7/RST_3") (pintype "bidirectional"))
    )
    (net (code "74") (name "unconnected-(U3-NC-Pad1)") (class "Default")
      (node (ref "U3") (pin "1") (pinfunction "NC_1") (pintype "passive+no_connect"))
    )
    (net (code "75") (name "unconnected-(U4-NC-Pad1)") (class "Default")
      (node (ref "U4") (pin "1") (pinfunction "NC_1") (pintype "passive+no_connect"))
    )
    (net (code "76") (name "unconnected-(U5-NC-Pad1)") (class "Default")
      (node (ref "U5") (pin "1") (pinfunction "NC_1") (pintype "passive+no_connect"))
    )
    (net (code "77") (name "unconnected-(U6-NC-Pad1)") (class "Default")
      (node (ref "U6") (pin "1") (pinfunction "NC_1") (pintype "passive+no_connect"))
    )
  )
)
